# joystikfix.net
KiCad netlist of a schematic drawn in EAGLE
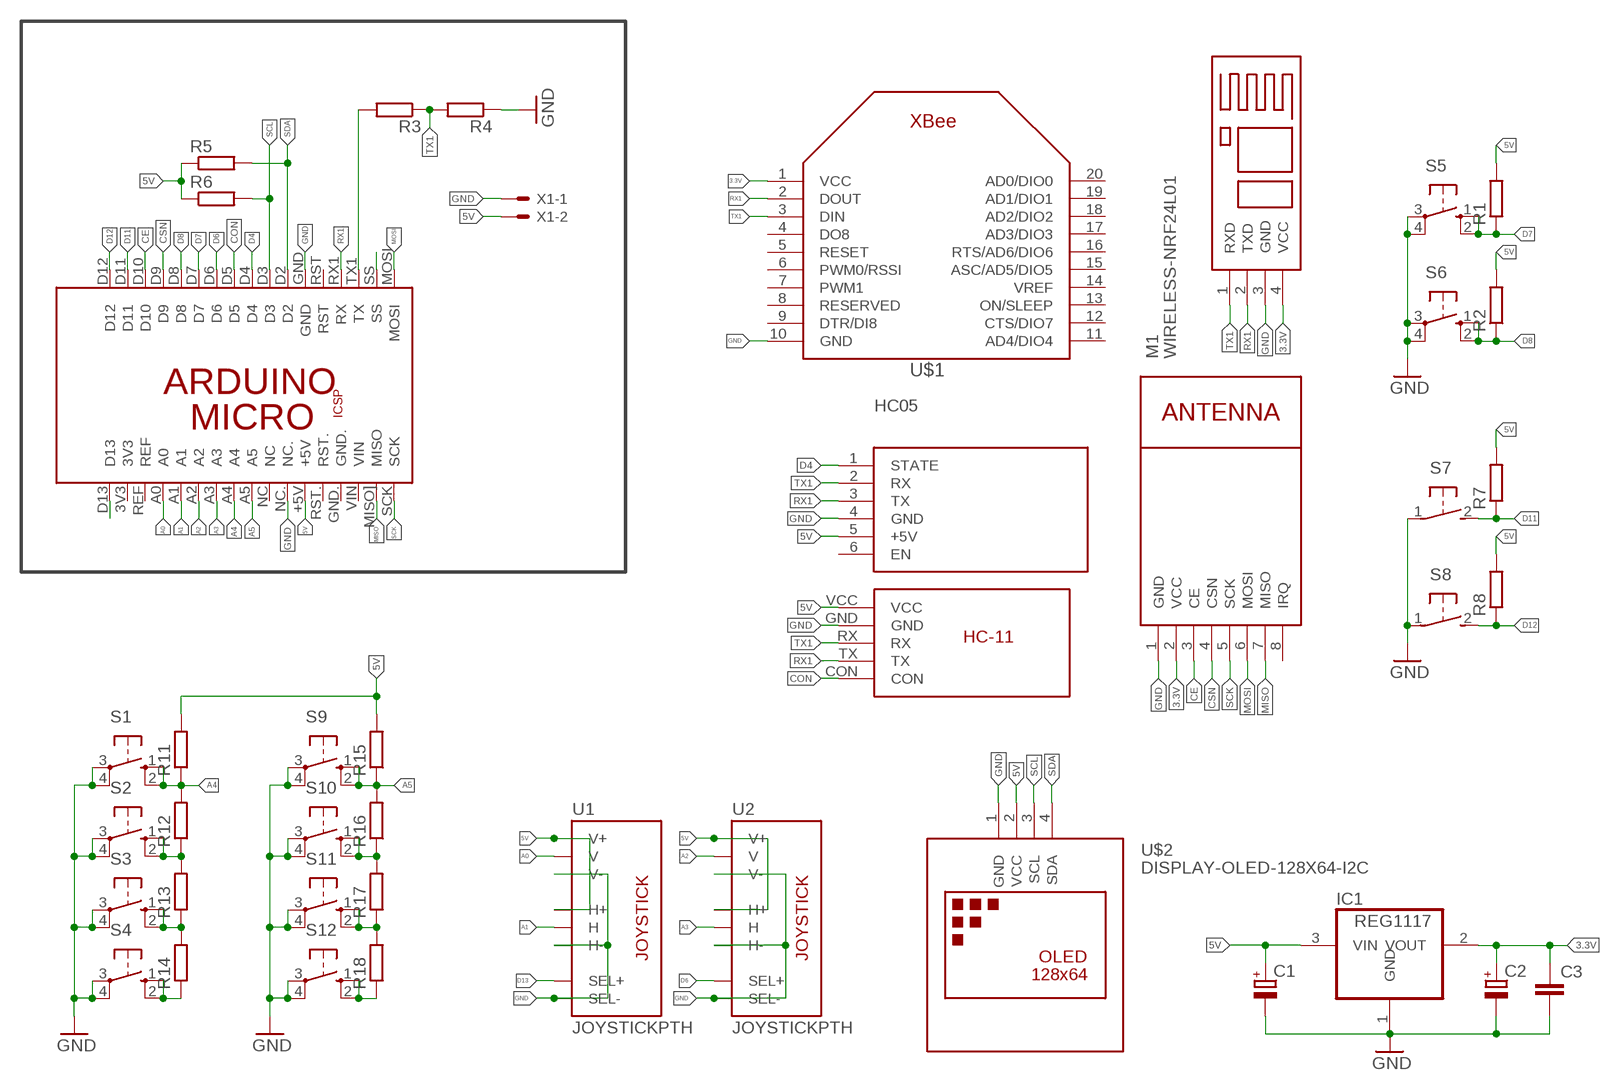
[diagram p0: schematic, sheet 1]

(export (version "E")
  (design (tool "Eeschema 10.0.6"))
  (components
    (comp (ref "C1")
      (value "CPOL-EUA/3216-18W")
      (footprint "eagle-import:A_3216-18W")
      (libsource (lib "eagle-import") (part "CPOL-EUA/3216-18W"))
    )
    (comp (ref "C2")
      (value "CPOL-EUA/3216-18W")
      (footprint "eagle-import:A_3216-18W")
      (libsource (lib "eagle-import") (part "CPOL-EUA/3216-18W"))
    )
    (comp (ref "C3")
      (value "C-EUC0805K")
      (footprint "eagle-import:C0805K")
      (libsource (lib "eagle-import") (part "C-EUC0805K"))
    )
    (comp (ref "HC05")
      (value "WIRELESS-BLUETOOTH-HC-05")
      (footprint "eagle-import:WIRELESS-BLUETOOTH-HC-05")
      (libsource (lib "eagle-import") (part "WIRELESS-BLUETOOTH-HC-05"))
    )
    (comp (ref "HM10")
      (value "BLUETOOTH")
      (footprint "eagle-import:BLUETOOTH")
      (libsource (lib "eagle-import") (part "BLUETOOTH"))
    )
    (comp (ref "IC1")
      (value "REG1117")
      (footprint "eagle-import:SOT223")
      (libsource (lib "eagle-import") (part "REG1117"))
    )
    (comp (ref "M1")
      (value "WIRELESS-NRF24L01")
      (footprint "eagle-import:WIRELESS-NRF24L01")
      (libsource (lib "eagle-import") (part "WIRELESS-NRF24L01"))
    )
    (comp (ref "PCB1")
      (value "ARDUINO_MICRO")
      (footprint "eagle-import:ARDUINO_MICRO")
      (libsource (lib "eagle-import") (part "ARDUINO_MICRO"))
    )
    (comp (ref "R1")
      (value "R-EU_M0805")
      (footprint "eagle-import:M0805")
      (libsource (lib "eagle-import") (part "R-EU_M0805"))
    )
    (comp (ref "R2")
      (value "R-EU_M0805")
      (footprint "eagle-import:M0805")
      (libsource (lib "eagle-import") (part "R-EU_M0805"))
    )
    (comp (ref "R3")
      (value "R-EU_M0805")
      (footprint "eagle-import:M0805")
      (libsource (lib "eagle-import") (part "R-EU_M0805"))
    )
    (comp (ref "R4")
      (value "R-EU_M0805")
      (footprint "eagle-import:M0805")
      (libsource (lib "eagle-import") (part "R-EU_M0805"))
    )
    (comp (ref "R5")
      (value "R-EU_M0805")
      (footprint "eagle-import:M0805")
      (libsource (lib "eagle-import") (part "R-EU_M0805"))
    )
    (comp (ref "R6")
      (value "R-EU_M0805")
      (footprint "eagle-import:M0805")
      (libsource (lib "eagle-import") (part "R-EU_M0805"))
    )
    (comp (ref "R7")
      (value "R-EU_M0805")
      (footprint "eagle-import:M0805")
      (libsource (lib "eagle-import") (part "R-EU_M0805"))
    )
    (comp (ref "R8")
      (value "R-EU_M0805")
      (footprint "eagle-import:M0805")
      (libsource (lib "eagle-import") (part "R-EU_M0805"))
    )
    (comp (ref "R11")
      (value "R-EU_M0805")
      (footprint "eagle-import:M0805")
      (libsource (lib "eagle-import") (part "R-EU_M0805"))
    )
    (comp (ref "R12")
      (value "R-EU_M0805")
      (footprint "eagle-import:M0805")
      (libsource (lib "eagle-import") (part "R-EU_M0805"))
    )
    (comp (ref "R13")
      (value "R-EU_M0805")
      (footprint "eagle-import:M0805")
      (libsource (lib "eagle-import") (part "R-EU_M0805"))
    )
    (comp (ref "R14")
      (value "R-EU_M0805")
      (footprint "eagle-import:M0805")
      (libsource (lib "eagle-import") (part "R-EU_M0805"))
    )
    (comp (ref "R15")
      (value "R-EU_M0805")
      (footprint "eagle-import:M0805")
      (libsource (lib "eagle-import") (part "R-EU_M0805"))
    )
    (comp (ref "R16")
      (value "R-EU_M0805")
      (footprint "eagle-import:M0805")
      (libsource (lib "eagle-import") (part "R-EU_M0805"))
    )
    (comp (ref "R17")
      (value "R-EU_M0805")
      (footprint "eagle-import:M0805")
      (libsource (lib "eagle-import") (part "R-EU_M0805"))
    )
    (comp (ref "R18")
      (value "R-EU_M0805")
      (footprint "eagle-import:M0805")
      (libsource (lib "eagle-import") (part "R-EU_M0805"))
    )
    (comp (ref "S1")
      (value "40-XX")
      (footprint "eagle-import:B3F-40XX")
      (fields (field (name "MF") "OMRON COMPONENTS USA") (field (name "MPN") "B3F-4000"))
      (libsource (lib "eagle-import") (part "40-XX"))
    )
    (comp (ref "S2")
      (value "40-XX")
      (footprint "eagle-import:B3F-40XX")
      (fields (field (name "MF") "OMRON COMPONENTS USA") (field (name "MPN") "B3F-4000"))
      (libsource (lib "eagle-import") (part "40-XX"))
    )
    (comp (ref "S3")
      (value "40-XX")
      (footprint "eagle-import:B3F-40XX")
      (fields (field (name "MF") "OMRON COMPONENTS USA") (field (name "MPN") "B3F-4000"))
      (libsource (lib "eagle-import") (part "40-XX"))
    )
    (comp (ref "S4")
      (value "40-XX")
      (footprint "eagle-import:B3F-40XX")
      (fields (field (name "MF") "OMRON COMPONENTS USA") (field (name "MPN") "B3F-4000"))
      (libsource (lib "eagle-import") (part "40-XX"))
    )
    (comp (ref "S5")
      (value "10-XX")
      (footprint "eagle-import:B3F-10XX")
      (fields (field (name "MPN") "B3F-1000"))
      (libsource (lib "eagle-import") (part "10-XX"))
    )
    (comp (ref "S6")
      (value "10-XX")
      (footprint "eagle-import:B3F-10XX")
      (fields (field (name "MPN") "B3F-1000"))
      (libsource (lib "eagle-import") (part "10-XX"))
    )
    (comp (ref "S7")
      (value "31-XX")
      (footprint "eagle-import:B3F-31XX")
      (fields (field (name "MPN") "B3F-3100"))
      (libsource (lib "eagle-import") (part "31-XX"))
    )
    (comp (ref "S8")
      (value "31-XX")
      (footprint "eagle-import:B3F-31XX")
      (fields (field (name "MPN") "B3F-3100"))
      (libsource (lib "eagle-import") (part "31-XX"))
    )
    (comp (ref "S9")
      (value "40-XX")
      (footprint "eagle-import:B3F-40XX")
      (fields (field (name "MF") "OMRON COMPONENTS USA") (field (name "MPN") "B3F-4000"))
      (libsource (lib "eagle-import") (part "40-XX"))
    )
    (comp (ref "S10")
      (value "40-XX")
      (footprint "eagle-import:B3F-40XX")
      (fields (field (name "MF") "OMRON COMPONENTS USA") (field (name "MPN") "B3F-4000"))
      (libsource (lib "eagle-import") (part "40-XX"))
    )
    (comp (ref "S11")
      (value "40-XX")
      (footprint "eagle-import:B3F-40XX")
      (fields (field (name "MF") "OMRON COMPONENTS USA") (field (name "MPN") "B3F-4000"))
      (libsource (lib "eagle-import") (part "40-XX"))
    )
    (comp (ref "S12")
      (value "40-XX")
      (footprint "eagle-import:B3F-40XX")
      (fields (field (name "MF") "OMRON COMPONENTS USA") (field (name "MPN") "B3F-4000"))
      (libsource (lib "eagle-import") (part "40-XX"))
    )
    (comp (ref "U$1")
      (value "XBEE")
      (footprint "eagle-import:XBEE")
      (libsource (lib "eagle-import") (part "XBEE"))
    )
    (comp (ref "U$2")
      (value "DISPLAY-OLED-128X64-I2C")
      (footprint "eagle-import:DISPLAY-OLED-128X64-I2C")
      (libsource (lib "eagle-import") (part "DISPLAY-OLED-128X64-I2C"))
    )
    (comp (ref "U$3")
      (value "HC-11")
      (footprint "eagle-import:HC-11")
      (libsource (lib "eagle-import") (part "HC-11"))
    )
    (comp (ref "U1")
      (value "JOYSTICKPTH")
      (footprint "eagle-import:JOYSTICK")
      (libsource (lib "eagle-import") (part "JOYSTICKPTH"))
    )
    (comp (ref "U2")
      (value "JOYSTICKPTH")
      (footprint "eagle-import:JOYSTICK")
      (libsource (lib "eagle-import") (part "JOYSTICKPTH"))
    )
    (comp (ref "X1")
      (value "22-23-2021")
      (footprint "eagle-import:22-23-2021")
      (fields (field (name "MF") "MOLEX"))
      (libsource (lib "eagle-import") (part "22-23-2021"))
    )
  )
  (nets
    (net (code "1") (name "3.3V") (class "Default")
      (node (ref "C2") (pin "+") (pinfunction "+_+") (pintype "passive"))
      (node (ref "C3") (pin "1") (pinfunction "1_1") (pintype "passive"))
      (node (ref "HM10") (pin "4") (pinfunction "VCC_4") (pintype "power_in"))
      (node (ref "IC1") (pin "2") (pinfunction "VOUT_2") (pintype "output"))
      (node (ref "M1") (pin "2") (pinfunction "VCC_2") (pintype "power_in"))
      (node (ref "U$1") (pin "1") (pinfunction "VCC_1") (pintype "power_in"))
    )
    (net (code "2") (name "5V") (class "Default")
      (node (ref "C1") (pin "+") (pinfunction "+_+") (pintype "passive"))
      (node (ref "HC05") (pin "5") (pinfunction "+5V_5") (pintype "power_in"))
      (node (ref "IC1") (pin "3") (pinfunction "VIN_3") (pintype "input"))
      (node (ref "PCB1") (pin "+5V") (pinfunction "+5V_+5V") (pintype "bidirectional"))
      (node (ref "R1") (pin "2") (pinfunction "2_2") (pintype "passive"))
      (node (ref "R11") (pin "2") (pinfunction "2_2") (pintype "passive"))
      (node (ref "R15") (pin "2") (pinfunction "2_2") (pintype "passive"))
      (node (ref "R2") (pin "2") (pinfunction "2_2") (pintype "passive"))
      (node (ref "R5") (pin "1") (pinfunction "1_1") (pintype "passive"))
      (node (ref "R6") (pin "1") (pinfunction "1_1") (pintype "passive"))
      (node (ref "R7") (pin "2") (pinfunction "2_2") (pintype "passive"))
      (node (ref "R8") (pin "2") (pinfunction "2_2") (pintype "passive"))
      (node (ref "U$2") (pin "2") (pinfunction "VCC_2") (pintype "power_in"))
      (node (ref "U$3") (pin "VCC") (pinfunction "VCC_VCC") (pintype "bidirectional"))
      (node (ref "U1") (pin "H1") (pinfunction "H+_H1") (pintype "bidirectional"))
      (node (ref "U1") (pin "V1") (pinfunction "V+_V1") (pintype "bidirectional"))
      (node (ref "U2") (pin "H1") (pinfunction "H+_H1") (pintype "bidirectional"))
      (node (ref "U2") (pin "V1") (pinfunction "V+_V1") (pintype "bidirectional"))
      (node (ref "X1") (pin "2") (pinfunction "S_2") (pintype "passive"))
    )
    (net (code "3") (name "A0") (class "Default")
      (node (ref "PCB1") (pin "A0") (pinfunction "A0_A0") (pintype "bidirectional"))
      (node (ref "U1") (pin "V2") (pinfunction "V_V2") (pintype "bidirectional"))
    )
    (net (code "4") (name "A1") (class "Default")
      (node (ref "PCB1") (pin "A1") (pinfunction "A1_A1") (pintype "bidirectional"))
      (node (ref "U1") (pin "H2") (pinfunction "H_H2") (pintype "bidirectional"))
    )
    (net (code "5") (name "A2") (class "Default")
      (node (ref "PCB1") (pin "A2") (pinfunction "A2_A2") (pintype "bidirectional"))
      (node (ref "U2") (pin "V2") (pinfunction "V_V2") (pintype "bidirectional"))
    )
    (net (code "6") (name "A3") (class "Default")
      (node (ref "PCB1") (pin "A3") (pinfunction "A3_A3") (pintype "bidirectional"))
      (node (ref "U2") (pin "H2") (pinfunction "H_H2") (pintype "bidirectional"))
    )
    (net (code "7") (name "A4") (class "Default")
      (node (ref "PCB1") (pin "A4") (pinfunction "A4_A4") (pintype "bidirectional"))
      (node (ref "R11") (pin "1") (pinfunction "1_1") (pintype "passive"))
      (node (ref "R12") (pin "2") (pinfunction "2_2") (pintype "passive"))
      (node (ref "S1") (pin "1") (pinfunction "S_1") (pintype "passive"))
      (node (ref "S1") (pin "2") (pinfunction "S1_2") (pintype "passive"))
    )
    (net (code "8") (name "A5") (class "Default")
      (node (ref "PCB1") (pin "A5") (pinfunction "A5_A5") (pintype "bidirectional"))
      (node (ref "R15") (pin "1") (pinfunction "1_1") (pintype "passive"))
      (node (ref "R16") (pin "2") (pinfunction "2_2") (pintype "passive"))
      (node (ref "S9") (pin "1") (pinfunction "S_1") (pintype "passive"))
      (node (ref "S9") (pin "2") (pinfunction "S1_2") (pintype "passive"))
    )
    (net (code "9") (name "CE") (class "Default")
      (node (ref "M1") (pin "3") (pinfunction "CE_3") (pintype "bidirectional"))
      (node (ref "PCB1") (pin "D10") (pinfunction "D10_D10") (pintype "bidirectional"))
    )
    (net (code "10") (name "CON") (class "Default")
      (node (ref "PCB1") (pin "D5") (pinfunction "D5_D5") (pintype "bidirectional"))
      (node (ref "U$3") (pin "CON") (pinfunction "CON_CON") (pintype "bidirectional"))
    )
    (net (code "11") (name "CSN") (class "Default")
      (node (ref "M1") (pin "4") (pinfunction "CSN_4") (pintype "bidirectional"))
      (node (ref "PCB1") (pin "D9") (pinfunction "D9_D9") (pintype "bidirectional"))
    )
    (net (code "12") (name "D4") (class "Default")
      (node (ref "HC05") (pin "1") (pinfunction "STATE_1") (pintype "bidirectional"))
      (node (ref "PCB1") (pin "D4") (pinfunction "D4_D4") (pintype "bidirectional"))
    )
    (net (code "13") (name "D6") (class "Default")
      (node (ref "PCB1") (pin "D6") (pinfunction "D6_D6") (pintype "bidirectional"))
      (node (ref "U2") (pin "B1A") (pinfunction "SEL+_B1A") (pintype "bidirectional"))
    )
    (net (code "14") (name "D7") (class "Default")
      (node (ref "PCB1") (pin "D7") (pinfunction "D7_D7") (pintype "bidirectional"))
      (node (ref "R1") (pin "1") (pinfunction "1_1") (pintype "passive"))
      (node (ref "S5") (pin "1") (pinfunction "S_1") (pintype "passive"))
      (node (ref "S5") (pin "2") (pinfunction "S1_2") (pintype "passive"))
    )
    (net (code "15") (name "D8") (class "Default")
      (node (ref "PCB1") (pin "D8") (pinfunction "D8_D8") (pintype "bidirectional"))
      (node (ref "R2") (pin "1") (pinfunction "1_1") (pintype "passive"))
      (node (ref "S6") (pin "1") (pinfunction "S_1") (pintype "passive"))
      (node (ref "S6") (pin "2") (pinfunction "S1_2") (pintype "passive"))
    )
    (net (code "16") (name "D11") (class "Default")
      (node (ref "PCB1") (pin "D11") (pinfunction "D11_D11") (pintype "bidirectional"))
      (node (ref "R7") (pin "1") (pinfunction "1_1") (pintype "passive"))
      (node (ref "S7") (pin "2") (pinfunction "S_2") (pintype "passive"))
    )
    (net (code "17") (name "D12") (class "Default")
      (node (ref "PCB1") (pin "D12") (pinfunction "D12_D12") (pintype "bidirectional"))
      (node (ref "R8") (pin "1") (pinfunction "1_1") (pintype "passive"))
      (node (ref "S8") (pin "2") (pinfunction "S_2") (pintype "passive"))
    )
    (net (code "18") (name "D13") (class "Default")
      (node (ref "PCB1") (pin "D13") (pinfunction "D13_D13") (pintype "bidirectional"))
      (node (ref "U1") (pin "B1A") (pinfunction "SEL+_B1A") (pintype "bidirectional"))
    )
    (net (code "19") (name "GND") (class "Default")
      (node (ref "C1") (pin "-") (pinfunction "-_-") (pintype "passive"))
      (node (ref "C2") (pin "-") (pinfunction "-_-") (pintype "passive"))
      (node (ref "C3") (pin "2") (pinfunction "2_2") (pintype "passive"))
      (node (ref "HC05") (pin "4") (pinfunction "GND_4") (pintype "power_in"))
      (node (ref "HM10") (pin "3") (pinfunction "GND_3") (pintype "power_in"))
      (node (ref "IC1") (pin "1") (pinfunction "GND_1") (pintype "power_in"))
      (node (ref "M1") (pin "1") (pinfunction "GND_1") (pintype "power_in"))
      (node (ref "PCB1") (pin "GND") (pinfunction "GND_GND") (pintype "bidirectional"))
      (node (ref "PCB1") (pin "NC.") (pinfunction "NC._NC.") (pintype "bidirectional"))
      (node (ref "R4") (pin "1") (pinfunction "1_1") (pintype "passive"))
      (node (ref "S1") (pin "3") (pinfunction "P_3") (pintype "passive"))
      (node (ref "S1") (pin "4") (pinfunction "P1_4") (pintype "passive"))
      (node (ref "S10") (pin "3") (pinfunction "P_3") (pintype "passive"))
      (node (ref "S10") (pin "4") (pinfunction "P1_4") (pintype "passive"))
      (node (ref "S11") (pin "3") (pinfunction "P_3") (pintype "passive"))
      (node (ref "S11") (pin "4") (pinfunction "P1_4") (pintype "passive"))
      (node (ref "S12") (pin "3") (pinfunction "P_3") (pintype "passive"))
      (node (ref "S12") (pin "4") (pinfunction "P1_4") (pintype "passive"))
      (node (ref "S2") (pin "3") (pinfunction "P_3") (pintype "passive"))
      (node (ref "S2") (pin "4") (pinfunction "P1_4") (pintype "passive"))
      (node (ref "S3") (pin "3") (pinfunction "P_3") (pintype "passive"))
      (node (ref "S3") (pin "4") (pinfunction "P1_4") (pintype "passive"))
      (node (ref "S4") (pin "3") (pinfunction "P_3") (pintype "passive"))
      (node (ref "S4") (pin "4") (pinfunction "P1_4") (pintype "passive"))
      (node (ref "S5") (pin "3") (pinfunction "P_3") (pintype "passive"))
      (node (ref "S5") (pin "4") (pinfunction "P1_4") (pintype "passive"))
      (node (ref "S6") (pin "3") (pinfunction "P_3") (pintype "passive"))
      (node (ref "S6") (pin "4") (pinfunction "P1_4") (pintype "passive"))
      (node (ref "S7") (pin "1") (pinfunction "P_1") (pintype "passive"))
      (node (ref "S8") (pin "1") (pinfunction "P_1") (pintype "passive"))
      (node (ref "S9") (pin "3") (pinfunction "P_3") (pintype "passive"))
      (node (ref "S9") (pin "4") (pinfunction "P1_4") (pintype "passive"))
      (node (ref "U$1") (pin "10") (pinfunction "GND_10") (pintype "power_in"))
      (node (ref "U$2") (pin "1") (pinfunction "GND_1") (pintype "power_in"))
      (node (ref "U$3") (pin "GND") (pinfunction "GND_GND") (pintype "bidirectional"))
      (node (ref "U1") (pin "B2A") (pinfunction "SEL-_B2A") (pintype "bidirectional"))
      (node (ref "U1") (pin "H3") (pinfunction "H-_H3") (pintype "bidirectional"))
      (node (ref "U1") (pin "V3") (pinfunction "V-_V3") (pintype "bidirectional"))
      (node (ref "U2") (pin "B2A") (pinfunction "SEL-_B2A") (pintype "bidirectional"))
      (node (ref "U2") (pin "H3") (pinfunction "H-_H3") (pintype "bidirectional"))
      (node (ref "U2") (pin "V3") (pinfunction "V-_V3") (pintype "bidirectional"))
      (node (ref "X1") (pin "1") (pinfunction "S_1") (pintype "passive"))
    )
    (net (code "20") (name "MISO") (class "Default")
      (node (ref "M1") (pin "7") (pinfunction "MISO_7") (pintype "bidirectional"))
      (node (ref "PCB1") (pin "MISO]") (pinfunction "MISO_MISO]") (pintype "bidirectional"))
    )
    (net (code "21") (name "MOSI") (class "Default")
      (node (ref "M1") (pin "6") (pinfunction "MOSI_6") (pintype "bidirectional"))
      (node (ref "PCB1") (pin "MOSI") (pinfunction "MOSI_MOSI") (pintype "bidirectional"))
    )
    (net (code "22") (name "Net-(PCB1-TX)") (class "Default")
      (node (ref "PCB1") (pin "TX1") (pinfunction "TX_TX1") (pintype "bidirectional"))
      (node (ref "R3") (pin "2") (pinfunction "2_2") (pintype "passive"))
    )
    (net (code "23") (name "Net-(S2-S)") (class "Default")
      (node (ref "R12") (pin "1") (pinfunction "1_1") (pintype "passive"))
      (node (ref "R13") (pin "2") (pinfunction "2_2") (pintype "passive"))
      (node (ref "S2") (pin "1") (pinfunction "S_1") (pintype "passive"))
      (node (ref "S2") (pin "2") (pinfunction "S1_2") (pintype "passive"))
    )
    (net (code "24") (name "Net-(S3-S)") (class "Default")
      (node (ref "R13") (pin "1") (pinfunction "1_1") (pintype "passive"))
      (node (ref "R14") (pin "2") (pinfunction "2_2") (pintype "passive"))
      (node (ref "S3") (pin "1") (pinfunction "S_1") (pintype "passive"))
      (node (ref "S3") (pin "2") (pinfunction "S1_2") (pintype "passive"))
    )
    (net (code "25") (name "Net-(S4-S)") (class "Default")
      (node (ref "R14") (pin "1") (pinfunction "1_1") (pintype "passive"))
      (node (ref "S4") (pin "1") (pinfunction "S_1") (pintype "passive"))
      (node (ref "S4") (pin "2") (pinfunction "S1_2") (pintype "passive"))
    )
    (net (code "26") (name "Net-(S10-S)") (class "Default")
      (node (ref "R16") (pin "1") (pinfunction "1_1") (pintype "passive"))
      (node (ref "R17") (pin "2") (pinfunction "2_2") (pintype "passive"))
      (node (ref "S10") (pin "1") (pinfunction "S_1") (pintype "passive"))
      (node (ref "S10") (pin "2") (pinfunction "S1_2") (pintype "passive"))
    )
    (net (code "27") (name "Net-(S11-S)") (class "Default")
      (node (ref "R17") (pin "1") (pinfunction "1_1") (pintype "passive"))
      (node (ref "R18") (pin "2") (pinfunction "2_2") (pintype "passive"))
      (node (ref "S11") (pin "1") (pinfunction "S_1") (pintype "passive"))
      (node (ref "S11") (pin "2") (pinfunction "S1_2") (pintype "passive"))
    )
    (net (code "28") (name "Net-(S12-S)") (class "Default")
      (node (ref "R18") (pin "1") (pinfunction "1_1") (pintype "passive"))
      (node (ref "S12") (pin "1") (pinfunction "S_1") (pintype "passive"))
      (node (ref "S12") (pin "2") (pinfunction "S1_2") (pintype "passive"))
    )
    (net (code "29") (name "RX1") (class "Default")
      (node (ref "HC05") (pin "3") (pinfunction "TX_3") (pintype "bidirectional"))
      (node (ref "HM10") (pin "2") (pinfunction "TXD_2") (pintype "bidirectional"))
      (node (ref "PCB1") (pin "RX1") (pinfunction "RX_RX1") (pintype "bidirectional"))
      (node (ref "U$1") (pin "2") (pinfunction "DOUT_2") (pintype "output"))
      (node (ref "U$3") (pin "TX") (pinfunction "TX_TX") (pintype "bidirectional"))
    )
    (net (code "30") (name "SCK") (class "Default")
      (node (ref "M1") (pin "5") (pinfunction "SCK_5") (pintype "bidirectional"))
      (node (ref "PCB1") (pin "SCK") (pinfunction "SCK_SCK") (pintype "bidirectional"))
    )
    (net (code "31") (name "SCL") (class "Default")
      (node (ref "PCB1") (pin "D3") (pinfunction "D3_D3") (pintype "bidirectional"))
      (node (ref "R6") (pin "2") (pinfunction "2_2") (pintype "passive"))
      (node (ref "U$2") (pin "3") (pinfunction "SCL_3") (pintype "bidirectional"))
    )
    (net (code "32") (name "SDA") (class "Default")
      (node (ref "PCB1") (pin "D2") (pinfunction "D2_D2") (pintype "bidirectional"))
      (node (ref "R5") (pin "2") (pinfunction "2_2") (pintype "passive"))
      (node (ref "U$2") (pin "4") (pinfunction "SDA_4") (pintype "bidirectional"))
    )
    (net (code "33") (name "TX1") (class "Default")
      (node (ref "HC05") (pin "2") (pinfunction "RX_2") (pintype "bidirectional"))
      (node (ref "HM10") (pin "1") (pinfunction "RXD_1") (pintype "bidirectional"))
      (node (ref "R3") (pin "1") (pinfunction "1_1") (pintype "passive"))
      (node (ref "R4") (pin "2") (pinfunction "2_2") (pintype "passive"))
      (node (ref "U$1") (pin "3") (pinfunction "DIN_3") (pintype "input"))
      (node (ref "U$3") (pin "RX") (pinfunction "RX_RX") (pintype "bidirectional"))
    )
    (net (code "34") (name "unconnected-(HC05-EN-Pad6)") (class "Default")
      (node (ref "HC05") (pin "6") (pinfunction "EN_6") (pintype "bidirectional"))
    )
    (net (code "35") (name "unconnected-(M1-IRQ-Pad8)") (class "Default")
      (node (ref "M1") (pin "8") (pinfunction "IRQ_8") (pintype "bidirectional"))
    )
    (net (code "36") (name "unconnected-(PCB1-Pad3V3)") (class "Default")
      (node (ref "PCB1") (pin "3V3") (pinfunction "3V3_3V3") (pintype "bidirectional"))
    )
    (net (code "37") (name "unconnected-(PCB1-PadGND.)") (class "Default")
      (node (ref "PCB1") (pin "GND.") (pinfunction "GND._GND.") (pintype "bidirectional"))
    )
    (net (code "38") (name "unconnected-(PCB1-PadNC)") (class "Default")
      (node (ref "PCB1") (pin "NC") (pinfunction "NC_NC") (pintype "bidirectional"))
    )
    (net (code "39") (name "unconnected-(PCB1-PadREF)") (class "Default")
      (node (ref "PCB1") (pin "REF") (pinfunction "REF_REF") (pintype "bidirectional"))
    )
    (net (code "40") (name "unconnected-(PCB1-PadRST)") (class "Default")
      (node (ref "PCB1") (pin "RST") (pinfunction "RST_RST") (pintype "bidirectional"))
    )
    (net (code "41") (name "unconnected-(PCB1-PadRST.)") (class "Default")
      (node (ref "PCB1") (pin "RST.") (pinfunction "RST._RST.") (pintype "bidirectional"))
    )
    (net (code "42") (name "unconnected-(PCB1-PadSS)") (class "Default")
      (node (ref "PCB1") (pin "SS") (pinfunction "SS_SS") (pintype "bidirectional"))
    )
    (net (code "43") (name "unconnected-(PCB1-PadVIN)") (class "Default")
      (node (ref "PCB1") (pin "VIN") (pinfunction "VIN_VIN") (pintype "bidirectional"))
    )
    (net (code "44") (name "unconnected-(U$1-AD0{slash}DIO0-Pad20)") (class "Default")
      (node (ref "U$1") (pin "20") (pinfunction "AD0/DIO0_20") (pintype "bidirectional"))
    )
    (net (code "45") (name "unconnected-(U$1-AD1{slash}DIO1-Pad19)") (class "Default")
      (node (ref "U$1") (pin "19") (pinfunction "AD1/DIO1_19") (pintype "bidirectional"))
    )
    (net (code "46") (name "unconnected-(U$1-AD2{slash}DIO2-Pad18)") (class "Default")
      (node (ref "U$1") (pin "18") (pinfunction "AD2/DIO2_18") (pintype "bidirectional"))
    )
    (net (code "47") (name "unconnected-(U$1-AD3{slash}DIO3-Pad17)") (class "Default")
      (node (ref "U$1") (pin "17") (pinfunction "AD3/DIO3_17") (pintype "bidirectional"))
    )
    (net (code "48") (name "unconnected-(U$1-AD4{slash}DIO4-Pad11)") (class "Default")
      (node (ref "U$1") (pin "11") (pinfunction "AD4/DIO4_11") (pintype "bidirectional"))
    )
    (net (code "49") (name "unconnected-(U$1-ASC{slash}AD5{slash}DIO5-Pad15)") (class "Default")
      (node (ref "U$1") (pin "15") (pinfunction "ASC/AD5/DIO5_15") (pintype "bidirectional"))
    )
    (net (code "50") (name "unconnected-(U$1-CTS{slash}DIO7-Pad12)") (class "Default")
      (node (ref "U$1") (pin "12") (pinfunction "CTS/DIO7_12") (pintype "bidirectional"))
    )
    (net (code "51") (name "unconnected-(U$1-DO8-Pad4)") (class "Default")
      (node (ref "U$1") (pin "4") (pinfunction "DO8_4") (pintype "output"))
    )
    (net (code "52") (name "unconnected-(U$1-DTR{slash}DI8-Pad9)") (class "Default")
      (node (ref "U$1") (pin "9") (pinfunction "DTR/DI8_9") (pintype "input"))
    )
    (net (code "53") (name "unconnected-(U$1-ON{slash}SLEEP-Pad13)") (class "Default")
      (node (ref "U$1") (pin "13") (pinfunction "ON/SLEEP_13") (pintype "output"))
    )
    (net (code "54") (name "unconnected-(U$1-PWM0{slash}RSSI-Pad6)") (class "Default")
      (node (ref "U$1") (pin "6") (pinfunction "PWM0/RSSI_6") (pintype "output"))
    )
    (net (code "55") (name "unconnected-(U$1-PWM1-Pad7)") (class "Default")
      (node (ref "U$1") (pin "7") (pinfunction "PWM1_7") (pintype "output"))
    )
    (net (code "56") (name "unconnected-(U$1-RESERVED-Pad8)") (class "Default")
      (node (ref "U$1") (pin "8") (pinfunction "RESERVED_8") (pintype "no_connect"))
    )
    (net (code "57") (name "unconnected-(U$1-RESET-Pad5)") (class "Default")
      (node (ref "U$1") (pin "5") (pinfunction "RESET_5") (pintype "input"))
    )
    (net (code "58") (name "unconnected-(U$1-RTS{slash}AD6{slash}DIO6-Pad16)") (class "Default")
      (node (ref "U$1") (pin "16") (pinfunction "RTS/AD6/DIO6_16") (pintype "bidirectional"))
    )
    (net (code "59") (name "unconnected-(U$1-VREF-Pad14)") (class "Default")
      (node (ref "U$1") (pin "14") (pinfunction "VREF_14") (pintype "input"))
    )
  )
)
